# V4-AddRS485-V01-012.net
KiCad netlist of a schematic drawn in EAGLE
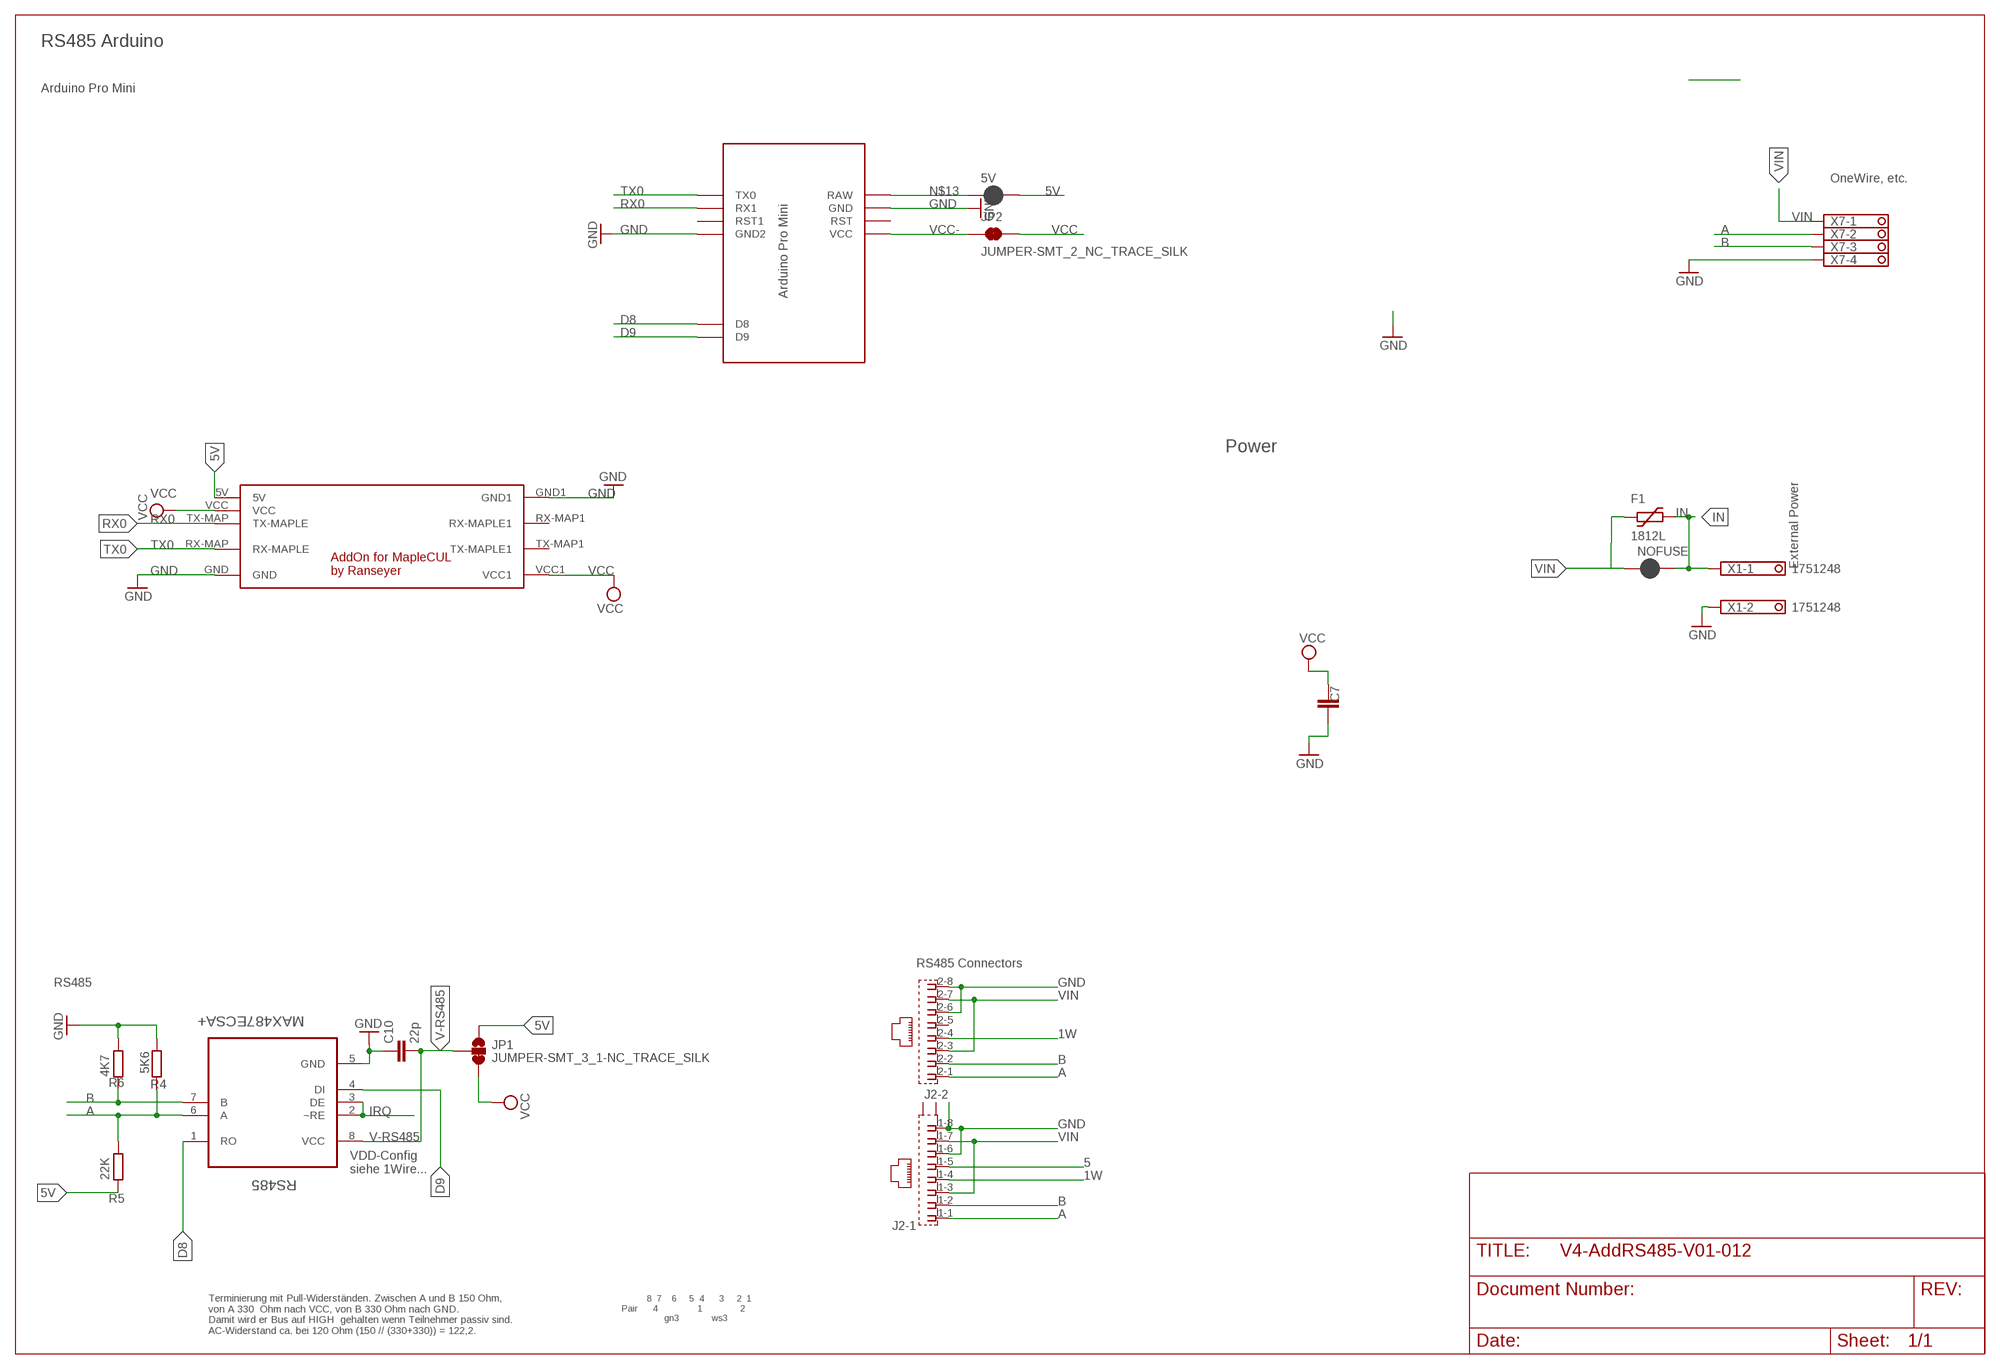
[diagram p0: schematic, sheet 1]

(export (version "E")
  (design (tool "Eeschema 10.0.6"))
  (components
    (comp (ref "5V")
      (value "JUMPER-SMT_2_NC_PASTE_NO-SILK")
      (footprint "eagle-import:SMT-JUMPER_2_NC_PASTE_NO-SILK")
      (libsource (lib "eagle-import") (part "JUMPER-SMT_2_NC_PASTE_NO-SILK"))
    )
    (comp (ref "C7")
      (value "C-EUC1812")
      (footprint "eagle-import:C1812")
      (libsource (lib "eagle-import") (part "rcl_334_C-EUC1812"))
    )
    (comp (ref "C10")
      (value "22p")
      (footprint "eagle-import:C0805")
      (libsource (lib "eagle-import") (part "C-EUC0805"))
    )
    (comp (ref "F1")
      (value "1812L")
      (footprint "eagle-import:1812L")
      (libsource (lib "eagle-import") (part "1812L"))
    )
    (comp (ref "J2")
      (value "RJ45_2X_S")
      (footprint "eagle-import:RJ45_2X_S")
      (libsource (lib "eagle-import") (part "RJ45_2X_S"))
    )
    (comp (ref "JP1")
      (value "JUMPER-SMT_3_1-NC_TRACE_SILK")
      (footprint "eagle-import:SMT-JUMPER_3_1-NC_TRACE_SILK")
      (libsource (lib "eagle-import") (part "JUMPER-SMT_3_1-NC_TRACE_SILK"))
    )
    (comp (ref "JP2")
      (value "JUMPER-SMT_2_NC_TRACE_SILK")
      (footprint "eagle-import:SMT-JUMPER_2_NC_TRACE_SILK")
      (libsource (lib "eagle-import") (part "JUMPER-SMT_2_NC_TRACE_SILK"))
    )
    (comp (ref "NOFUSE")
      (value "JUMPER-SMT_2_NC_PASTE_NO-SILK")
      (footprint "eagle-import:SMT-JUMPER_2_NC_PASTE_NO-SILK")
      (libsource (lib "eagle-import") (part "JUMPER-SMT_2_NC_PASTE_NO-SILK"))
    )
    (comp (ref "R4")
      (value "5K6")
      (footprint "eagle-import:R0805")
      (libsource (lib "eagle-import") (part "R-EU_R0805"))
    )
    (comp (ref "R5")
      (value "22K")
      (footprint "eagle-import:R0805")
      (libsource (lib "eagle-import") (part "R-EU_R0805"))
    )
    (comp (ref "R6")
      (value "4K7")
      (footprint "eagle-import:R0805")
      (libsource (lib "eagle-import") (part "R-EU_R0805"))
    )
    (comp (ref "RS485")
      (value "MAX487ECSA+")
      (footprint "eagle-import:SOIC127P600X175-8N")
      (libsource (lib "eagle-import") (part "MAX487ECSA+"))
    )
    (comp (ref "U$2")
      (value "MAPLE-CUL-ADDON-V01")
      (footprint "eagle-import:MAPLE-CUL-V01")
      (libsource (lib "eagle-import") (part "MAPLE-CUL-ADDON-V01"))
    )
    (comp (ref "U$3")
      (value "MARTIN-PRO-MINI-RS485")
      (footprint "eagle-import:MARTIN-PRO-MINI-RS485")
      (libsource (lib "eagle-import") (part "MARTIN-PRO-MINI-RS485"))
    )
    (comp (ref "X1")
      (value "1751248")
      (footprint "eagle-import:1751248")
      (libsource (lib "eagle-import") (part "1751248"))
    )
    (comp (ref "X7")
      (value "1751264")
      (footprint "eagle-import:1751264")
      (libsource (lib "eagle-import") (part "1751264"))
    )
  )
  (nets
    (net (code "1") (name "/1W") (class "Default")
      (node (ref "J2") (pin "1-4") (pinfunction "4_1-4") (pintype "passive"))
      (node (ref "J2") (pin "2-4") (pinfunction "4_2-4") (pintype "passive"))
    )
    (net (code "2") (name "/5") (class "Default")
      (node (ref "J2") (pin "1-5") (pinfunction "5_1-5") (pintype "passive"))
    )
    (net (code "3") (name "/A") (class "Default")
      (node (ref "J2") (pin "1-1") (pinfunction "1_1-1") (pintype "passive"))
      (node (ref "J2") (pin "2-1") (pinfunction "1_2-1") (pintype "passive"))
      (node (ref "R4") (pin "2") (pinfunction "2_2") (pintype "passive"))
      (node (ref "R5") (pin "2") (pinfunction "2_2") (pintype "passive"))
      (node (ref "RS485") (pin "6") (pinfunction "A_6") (pintype "bidirectional"))
      (node (ref "X7") (pin "2") (pinfunction "K_2") (pintype "passive"))
    )
    (net (code "4") (name "/B") (class "Default")
      (node (ref "J2") (pin "1-2") (pinfunction "2_1-2") (pintype "passive"))
      (node (ref "J2") (pin "2-2") (pinfunction "2_2-2") (pintype "passive"))
      (node (ref "R6") (pin "1") (pinfunction "1_1") (pintype "passive"))
      (node (ref "RS485") (pin "7") (pinfunction "B_7") (pintype "bidirectional"))
      (node (ref "X7") (pin "3") (pinfunction "K_3") (pintype "passive"))
    )
    (net (code "5") (name "/IRQ") (class "Default")
      (node (ref "RS485") (pin "2") (pinfunction "~{RE}_2") (pintype "input"))
      (node (ref "RS485") (pin "3") (pinfunction "DE_3") (pintype "input"))
    )
    (net (code "6") (name "/N$13") (class "Default")
      (node (ref "5V") (pin "1") (pinfunction "1_1") (pintype "passive"))
      (node (ref "U$3") (pin "RAW") (pinfunction "RAW_RAW") (pintype "bidirectional"))
    )
    (net (code "7") (name "/VCC-") (class "Default")
      (node (ref "JP2") (pin "1") (pinfunction "1_1") (pintype "passive"))
      (node (ref "U$3") (pin "VCC") (pinfunction "VCC_VCC") (pintype "bidirectional"))
    )
    (net (code "8") (name "5V") (class "Default")
      (node (ref "5V") (pin "2") (pinfunction "2_2") (pintype "passive"))
      (node (ref "JP1") (pin "1") (pinfunction "1_1") (pintype "passive"))
      (node (ref "R5") (pin "1") (pinfunction "1_1") (pintype "passive"))
      (node (ref "U$2") (pin "5V") (pinfunction "5V_5V") (pintype "bidirectional"))
    )
    (net (code "9") (name "D8") (class "Default")
      (node (ref "RS485") (pin "1") (pinfunction "RO_1") (pintype "output"))
      (node (ref "U$3") (pin "D8") (pinfunction "D8_D8") (pintype "bidirectional"))
    )
    (net (code "10") (name "D9") (class "Default")
      (node (ref "RS485") (pin "4") (pinfunction "DI_4") (pintype "input"))
      (node (ref "U$3") (pin "D9") (pinfunction "D9_D9") (pintype "bidirectional"))
    )
    (net (code "11") (name "GND") (class "Default")
      (node (ref "C10") (pin "1") (pinfunction "1_1") (pintype "passive"))
      (node (ref "C7") (pin "1") (pinfunction "1_1") (pintype "passive"))
      (node (ref "J2") (pin "1-6") (pinfunction "6_1-6") (pintype "passive"))
      (node (ref "J2") (pin "1-8") (pinfunction "8_1-8") (pintype "passive"))
      (node (ref "J2") (pin "2-6") (pinfunction "6_2-6") (pintype "passive"))
      (node (ref "J2") (pin "2-8") (pinfunction "8_2-8") (pintype "passive"))
      (node (ref "R4") (pin "1") (pinfunction "1_1") (pintype "passive"))
      (node (ref "R6") (pin "2") (pinfunction "2_2") (pintype "passive"))
      (node (ref "RS485") (pin "5") (pinfunction "GND_5") (pintype "passive"))
      (node (ref "U$2") (pin "GND") (pinfunction "GND_GND") (pintype "bidirectional"))
      (node (ref "U$2") (pin "GND1") (pinfunction "GND1_GND1") (pintype "bidirectional"))
      (node (ref "U$3") (pin "GND") (pinfunction "GND_GND") (pintype "bidirectional"))
      (node (ref "U$3") (pin "GND1") (pinfunction "GND2_GND1") (pintype "bidirectional"))
      (node (ref "X1") (pin "2") (pinfunction "K_2") (pintype "passive"))
      (node (ref "X7") (pin "4") (pinfunction "K_4") (pintype "passive"))
    )
    (net (code "12") (name "IN") (class "Default")
      (node (ref "F1") (pin "P$2") (pinfunction "2_P$2") (pintype "passive"))
      (node (ref "NOFUSE") (pin "2") (pinfunction "2_2") (pintype "passive"))
      (node (ref "X1") (pin "1") (pinfunction "K_1") (pintype "passive"))
    )
    (net (code "13") (name "RX0") (class "Default")
      (node (ref "U$2") (pin "TX-MAP") (pinfunction "TX-MAPLE_TX-MAP") (pintype "bidirectional"))
      (node (ref "U$3") (pin "RX1") (pinfunction "RX1_RX1") (pintype "bidirectional"))
    )
    (net (code "14") (name "TX0") (class "Default")
      (node (ref "U$2") (pin "RX-MAP") (pinfunction "RX-MAPLE_RX-MAP") (pintype "bidirectional"))
      (node (ref "U$3") (pin "TX0") (pinfunction "TX0_TX0") (pintype "bidirectional"))
    )
    (net (code "15") (name "V-RS485") (class "Default")
      (node (ref "C10") (pin "2") (pinfunction "2_2") (pintype "passive"))
      (node (ref "JP1") (pin "2") (pinfunction "2_2") (pintype "passive"))
      (node (ref "RS485") (pin "8") (pinfunction "VCC_8") (pintype "power_in"))
    )
    (net (code "16") (name "VCC") (class "Default")
      (node (ref "C7") (pin "2") (pinfunction "2_2") (pintype "passive"))
      (node (ref "JP1") (pin "3") (pinfunction "3_3") (pintype "passive"))
      (node (ref "JP2") (pin "2") (pinfunction "2_2") (pintype "passive"))
      (node (ref "U$2") (pin "VCC") (pinfunction "VCC_VCC") (pintype "bidirectional"))
      (node (ref "U$2") (pin "VCC1") (pinfunction "VCC1_VCC1") (pintype "bidirectional"))
    )
    (net (code "17") (name "VIN") (class "Default")
      (node (ref "F1") (pin "P$1") (pinfunction "1_P$1") (pintype "passive"))
      (node (ref "J2") (pin "1-3") (pinfunction "3_1-3") (pintype "passive"))
      (node (ref "J2") (pin "1-7") (pinfunction "7_1-7") (pintype "passive"))
      (node (ref "J2") (pin "2-3") (pinfunction "3_2-3") (pintype "passive"))
      (node (ref "J2") (pin "2-7") (pinfunction "7_2-7") (pintype "passive"))
      (node (ref "NOFUSE") (pin "1") (pinfunction "1_1") (pintype "passive"))
      (node (ref "X7") (pin "1") (pinfunction "K_1") (pintype "passive"))
    )
    (net (code "18") (name "unconnected-(J2A-S1-PadG3)") (class "Default")
      (node (ref "J2") (pin "G3") (pinfunction "S1_G3") (pintype "passive"))
    )
    (net (code "19") (name "unconnected-(J2A-S2-PadG1)") (class "Default")
      (node (ref "J2") (pin "G1") (pinfunction "S2_G1") (pintype "passive"))
    )
    (net (code "20") (name "unconnected-(J2B-5-Pad2-5)") (class "Default")
      (node (ref "J2") (pin "2-5") (pinfunction "5_2-5") (pintype "passive"))
    )
    (net (code "21") (name "unconnected-(U$2-RX-MAPLE1-PadRX-MAP1)") (class "Default")
      (node (ref "U$2") (pin "RX-MAP1") (pinfunction "RX-MAPLE1_RX-MAP1") (pintype "bidirectional"))
    )
    (net (code "22") (name "unconnected-(U$2-TX-MAPLE1-PadTX-MAP1)") (class "Default")
      (node (ref "U$2") (pin "TX-MAP1") (pinfunction "TX-MAPLE1_TX-MAP1") (pintype "bidirectional"))
    )
    (net (code "23") (name "unconnected-(U$3-PadRST)") (class "Default")
      (node (ref "U$3") (pin "RST") (pinfunction "RST_RST") (pintype "bidirectional"))
    )
    (net (code "24") (name "unconnected-(U$3-PadRST1)") (class "Default")
      (node (ref "U$3") (pin "RST1") (pinfunction "RST1_RST1") (pintype "bidirectional"))
    )
  )
)
